# alimentadorV5.net
KiCad netlist of a schematic drawn in EAGLE
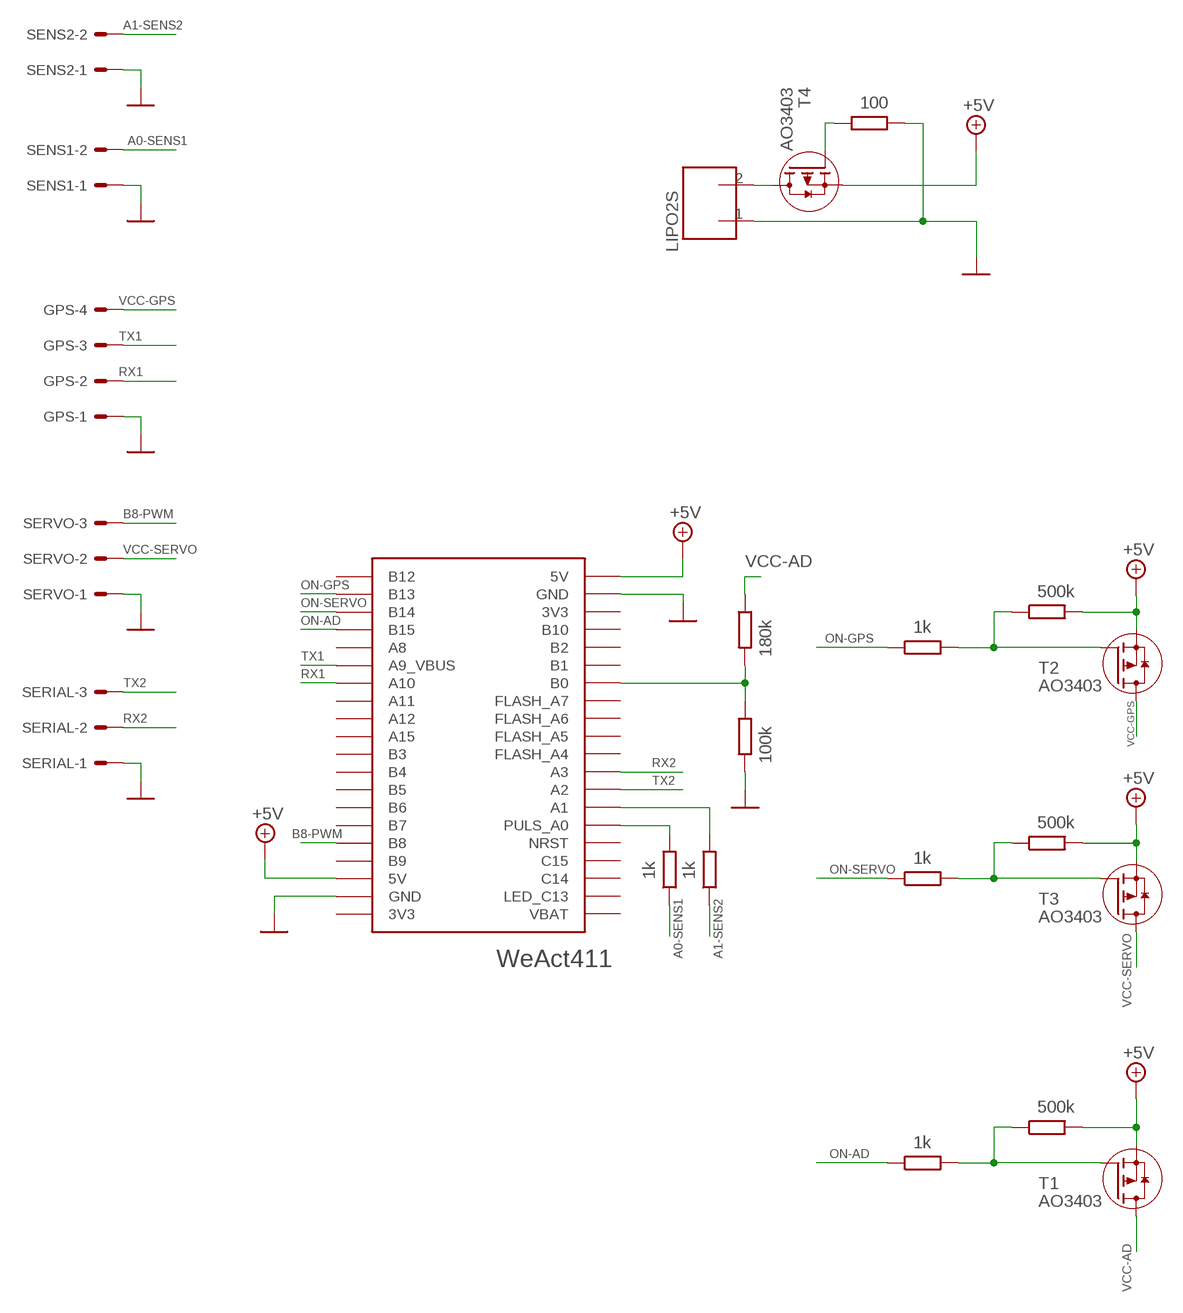
[diagram p0: schematic, sheet 1]

(export (version "E")
  (design (tool "Eeschema 10.0.6"))
  (components
    (comp (ref "GPS")
      (value "22-27-2041-04")
      (footprint "eagle-import:6410-04")
      (libsource (lib "eagle-import") (part "22-?-0427-2041"))
    )
    (comp (ref "LIPO2S")
      (value "CONECTOR_2P-3.81")
      (footprint "eagle-import:CON2P-3.81")
      (libsource (lib "eagle-import") (part "CONECTOR_2P-3.81"))
    )
    (comp (ref "R1")
      (value "500k")
      (footprint "eagle-import:R1206")
      (libsource (lib "eagle-import") (part "R-EU_R1206"))
    )
    (comp (ref "R2")
      (value "100k")
      (footprint "eagle-import:R1206")
      (libsource (lib "eagle-import") (part "R-EU_R1206"))
    )
    (comp (ref "R3")
      (value "180k")
      (footprint "eagle-import:R1206")
      (libsource (lib "eagle-import") (part "R-EU_R1206"))
    )
    (comp (ref "R4")
      (value "1k")
      (footprint "eagle-import:R1206")
      (libsource (lib "eagle-import") (part "R-EU_R1206"))
    )
    (comp (ref "R5")
      (value "500k")
      (footprint "eagle-import:R1206")
      (libsource (lib "eagle-import") (part "R-EU_R1206"))
    )
    (comp (ref "R6")
      (value "1k")
      (footprint "eagle-import:R1206")
      (libsource (lib "eagle-import") (part "R-EU_R1206"))
    )
    (comp (ref "R7")
      (value "100")
      (footprint "eagle-import:R1206")
      (libsource (lib "eagle-import") (part "R-EU_R1206"))
    )
    (comp (ref "R11")
      (value "500k")
      (footprint "eagle-import:R1206")
      (libsource (lib "eagle-import") (part "R-EU_R1206"))
    )
    (comp (ref "R12")
      (value "1k")
      (footprint "eagle-import:R1206")
      (libsource (lib "eagle-import") (part "R-EU_R1206"))
    )
    (comp (ref "R13")
      (value "1k")
      (footprint "eagle-import:R1206")
      (libsource (lib "eagle-import") (part "R-EU_R1206"))
    )
    (comp (ref "R14")
      (value "1k")
      (footprint "eagle-import:R1206")
      (libsource (lib "eagle-import") (part "R-EU_R1206"))
    )
    (comp (ref "SENS1")
      (value "22-27-2021-02")
      (footprint "eagle-import:6410-02")
      (libsource (lib "eagle-import") (part "22-?-0227-2021"))
    )
    (comp (ref "SENS2")
      (value "22-27-2021-02")
      (footprint "eagle-import:6410-02")
      (libsource (lib "eagle-import") (part "22-?-0227-2021"))
    )
    (comp (ref "SERIAL")
      (value "22-27-2031-03")
      (footprint "eagle-import:6410-03")
      (libsource (lib "eagle-import") (part "22-?-0327-2031"))
    )
    (comp (ref "SERVO")
      (value "22-27-2031-03")
      (footprint "eagle-import:6410-03")
      (libsource (lib "eagle-import") (part "22-?-0327-2031"))
    )
    (comp (ref "T1")
      (value "AO3403")
      (footprint "eagle-import:SOT23")
      (libsource (lib "eagle-import") (part "AO3403"))
    )
    (comp (ref "T2")
      (value "AO3403")
      (footprint "eagle-import:SOT23")
      (libsource (lib "eagle-import") (part "AO3403"))
    )
    (comp (ref "T3")
      (value "AO3403")
      (footprint "eagle-import:SOT23")
      (libsource (lib "eagle-import") (part "AO3403"))
    )
    (comp (ref "T4")
      (value "AO3403")
      (footprint "eagle-import:SOT23")
      (libsource (lib "eagle-import") (part "AO3403"))
    )
    (comp (ref "U$2")
      (value "WEACT411")
      (footprint "eagle-import:WEACT411")
      (libsource (lib "eagle-import") (part "WEACT411"))
    )
  )
  (nets
    (net (code "1") (name "+5V") (class "Default")
      (node (ref "R1") (pin "2") (pinfunction "2_2") (pintype "passive"))
      (node (ref "R11") (pin "2") (pinfunction "2_2") (pintype "passive"))
      (node (ref "R5") (pin "2") (pinfunction "2_2") (pintype "passive"))
      (node (ref "T1") (pin "2") (pinfunction "S_2") (pintype "passive"))
      (node (ref "T2") (pin "2") (pinfunction "S_2") (pintype "passive"))
      (node (ref "T3") (pin "2") (pinfunction "S_2") (pintype "passive"))
      (node (ref "T4") (pin "2") (pinfunction "S_2") (pintype "passive"))
      (node (ref "U$2") (pin "5V@1") (pinfunction "5V_5V@1") (pintype "power_in"))
      (node (ref "U$2") (pin "5V@2") (pinfunction "5V_5V@2") (pintype "power_in"))
    )
    (net (code "2") (name "/A0-SENS1") (class "Default")
      (node (ref "R13") (pin "1") (pinfunction "1_1") (pintype "passive"))
      (node (ref "SENS1") (pin "2") (pinfunction "S_2") (pintype "passive"))
    )
    (net (code "3") (name "/A1-SENS2") (class "Default")
      (node (ref "R14") (pin "1") (pinfunction "1_1") (pintype "passive"))
      (node (ref "SENS2") (pin "2") (pinfunction "S_2") (pintype "passive"))
    )
    (net (code "4") (name "/B8-PWM") (class "Default")
      (node (ref "SERVO") (pin "3") (pinfunction "S_3") (pintype "passive"))
      (node (ref "U$2") (pin "B8") (pinfunction "B8_B8") (pintype "bidirectional"))
    )
    (net (code "5") (name "/ON-AD") (class "Default")
      (node (ref "R12") (pin "1") (pinfunction "1_1") (pintype "passive"))
      (node (ref "U$2") (pin "B15") (pinfunction "B15_B15") (pintype "bidirectional"))
    )
    (net (code "6") (name "/ON-GPS") (class "Default")
      (node (ref "R4") (pin "1") (pinfunction "1_1") (pintype "passive"))
      (node (ref "U$2") (pin "B13") (pinfunction "B13_B13") (pintype "bidirectional"))
    )
    (net (code "7") (name "/ON-SERVO") (class "Default")
      (node (ref "R6") (pin "1") (pinfunction "1_1") (pintype "passive"))
      (node (ref "U$2") (pin "B14") (pinfunction "B14_B14") (pintype "bidirectional"))
    )
    (net (code "8") (name "/RX1") (class "Default")
      (node (ref "GPS") (pin "2") (pinfunction "S_2") (pintype "passive"))
      (node (ref "U$2") (pin "A10") (pinfunction "A10_A10") (pintype "bidirectional"))
    )
    (net (code "9") (name "/RX2") (class "Default")
      (node (ref "SERIAL") (pin "2") (pinfunction "S_2") (pintype "passive"))
      (node (ref "U$2") (pin "A3") (pinfunction "A3_A3") (pintype "bidirectional"))
    )
    (net (code "10") (name "/TX1") (class "Default")
      (node (ref "GPS") (pin "3") (pinfunction "S_3") (pintype "passive"))
      (node (ref "U$2") (pin "A9") (pinfunction "A9_VBUS_A9") (pintype "bidirectional"))
    )
    (net (code "11") (name "/TX2") (class "Default")
      (node (ref "SERIAL") (pin "3") (pinfunction "S_3") (pintype "passive"))
      (node (ref "U$2") (pin "A2") (pinfunction "A2_A2") (pintype "bidirectional"))
    )
    (net (code "12") (name "/VBAT") (class "Default")
      (node (ref "U$2") (pin "VBAT") (pinfunction "VBAT_VBAT") (pintype "power_in"))
    )
    (net (code "13") (name "/VCC-AD") (class "Default")
      (node (ref "R3") (pin "1") (pinfunction "1_1") (pintype "passive"))
      (node (ref "T1") (pin "3") (pinfunction "D_3") (pintype "passive"))
    )
    (net (code "14") (name "/VCC-GPS") (class "Default")
      (node (ref "GPS") (pin "4") (pinfunction "S_4") (pintype "passive"))
      (node (ref "T2") (pin "3") (pinfunction "D_3") (pintype "passive"))
    )
    (net (code "15") (name "/VCC-SERVO") (class "Default")
      (node (ref "SERVO") (pin "2") (pinfunction "S_2") (pintype "passive"))
      (node (ref "T3") (pin "3") (pinfunction "D_3") (pintype "passive"))
    )
    (net (code "16") (name "GND") (class "Default")
      (node (ref "GPS") (pin "1") (pinfunction "S_1") (pintype "passive"))
      (node (ref "LIPO2S") (pin "1") (pinfunction "1_1") (pintype "bidirectional"))
      (node (ref "R2") (pin "2") (pinfunction "2_2") (pintype "passive"))
      (node (ref "R7") (pin "2") (pinfunction "2_2") (pintype "passive"))
      (node (ref "SENS1") (pin "1") (pinfunction "S_1") (pintype "passive"))
      (node (ref "SENS2") (pin "1") (pinfunction "S_1") (pintype "passive"))
      (node (ref "SERIAL") (pin "1") (pinfunction "S_1") (pintype "passive"))
      (node (ref "SERVO") (pin "1") (pinfunction "S_1") (pintype "passive"))
      (node (ref "U$2") (pin "GND@1") (pinfunction "GND_GND@1") (pintype "power_in"))
      (node (ref "U$2") (pin "GND@2") (pinfunction "GND_GND@2") (pintype "power_in"))
    )
    (net (code "17") (name "Net-(R2-Pad1)") (class "Default")
      (node (ref "R2") (pin "1") (pinfunction "1_1") (pintype "passive"))
      (node (ref "R3") (pin "2") (pinfunction "2_2") (pintype "passive"))
      (node (ref "U$2") (pin "B0") (pinfunction "B0_B0") (pintype "bidirectional"))
    )
    (net (code "18") (name "Net-(R14-Pad2)") (class "Default")
      (node (ref "R14") (pin "2") (pinfunction "2_2") (pintype "passive"))
      (node (ref "U$2") (pin "A1") (pinfunction "A1_A1") (pintype "bidirectional"))
    )
    (net (code "19") (name "Net-(T1-G)") (class "Default")
      (node (ref "R11") (pin "1") (pinfunction "1_1") (pintype "passive"))
      (node (ref "R12") (pin "2") (pinfunction "2_2") (pintype "passive"))
      (node (ref "T1") (pin "1") (pinfunction "G_1") (pintype "passive"))
    )
    (net (code "20") (name "Net-(T2-G)") (class "Default")
      (node (ref "R1") (pin "1") (pinfunction "1_1") (pintype "passive"))
      (node (ref "R4") (pin "2") (pinfunction "2_2") (pintype "passive"))
      (node (ref "T2") (pin "1") (pinfunction "G_1") (pintype "passive"))
    )
    (net (code "21") (name "Net-(T3-G)") (class "Default")
      (node (ref "R5") (pin "1") (pinfunction "1_1") (pintype "passive"))
      (node (ref "R6") (pin "2") (pinfunction "2_2") (pintype "passive"))
      (node (ref "T3") (pin "1") (pinfunction "G_1") (pintype "passive"))
    )
    (net (code "22") (name "Net-(T4-D)") (class "Default")
      (node (ref "LIPO2S") (pin "2") (pinfunction "2_2") (pintype "bidirectional"))
      (node (ref "T4") (pin "3") (pinfunction "D_3") (pintype "passive"))
    )
    (net (code "23") (name "Net-(T4-G)") (class "Default")
      (node (ref "R7") (pin "1") (pinfunction "1_1") (pintype "passive"))
      (node (ref "T4") (pin "1") (pinfunction "G_1") (pintype "passive"))
    )
    (net (code "24") (name "Net-(U$2-PULS_A0)") (class "Default")
      (node (ref "R13") (pin "2") (pinfunction "2_2") (pintype "passive"))
      (node (ref "U$2") (pin "A0") (pinfunction "PULS_A0_A0") (pintype "bidirectional"))
    )
    (net (code "25") (name "unconnected-(U$2-3V3-Pad3V3@1)") (class "Default")
      (node (ref "U$2") (pin "3V3@1") (pinfunction "3V3_3V3@1") (pintype "bidirectional"))
    )
    (net (code "26") (name "unconnected-(U$2-3V3-Pad3V3@2)") (class "Default")
      (node (ref "U$2") (pin "3V3@2") (pinfunction "3V3_3V3@2") (pintype "bidirectional"))
    )
    (net (code "27") (name "unconnected-(U$2-FLASH_A4-PadA4)") (class "Default")
      (node (ref "U$2") (pin "A4") (pinfunction "FLASH_A4_A4") (pintype "bidirectional"))
    )
    (net (code "28") (name "unconnected-(U$2-FLASH_A5-PadA5)") (class "Default")
      (node (ref "U$2") (pin "A5") (pinfunction "FLASH_A5_A5") (pintype "bidirectional"))
    )
    (net (code "29") (name "unconnected-(U$2-FLASH_A6-PadA6)") (class "Default")
      (node (ref "U$2") (pin "A6") (pinfunction "FLASH_A6_A6") (pintype "bidirectional"))
    )
    (net (code "30") (name "unconnected-(U$2-FLASH_A7-PadA7)") (class "Default")
      (node (ref "U$2") (pin "A7") (pinfunction "FLASH_A7_A7") (pintype "bidirectional"))
    )
    (net (code "31") (name "unconnected-(U$2-LED_C13-PadC13)") (class "Default")
      (node (ref "U$2") (pin "C13") (pinfunction "LED_C13_C13") (pintype "bidirectional"))
    )
    (net (code "32") (name "unconnected-(U$2-PadA8)") (class "Default")
      (node (ref "U$2") (pin "A8") (pinfunction "A8_A8") (pintype "bidirectional"))
    )
    (net (code "33") (name "unconnected-(U$2-PadA11)") (class "Default")
      (node (ref "U$2") (pin "A11") (pinfunction "A11_A11") (pintype "bidirectional"))
    )
    (net (code "34") (name "unconnected-(U$2-PadA12)") (class "Default")
      (node (ref "U$2") (pin "A12") (pinfunction "A12_A12") (pintype "bidirectional"))
    )
    (net (code "35") (name "unconnected-(U$2-PadA15)") (class "Default")
      (node (ref "U$2") (pin "A15") (pinfunction "A15_A15") (pintype "bidirectional"))
    )
    (net (code "36") (name "unconnected-(U$2-PadB1)") (class "Default")
      (node (ref "U$2") (pin "B1") (pinfunction "B1_B1") (pintype "bidirectional"))
    )
    (net (code "37") (name "unconnected-(U$2-PadB2)") (class "Default")
      (node (ref "U$2") (pin "B2") (pinfunction "B2_B2") (pintype "bidirectional"))
    )
    (net (code "38") (name "unconnected-(U$2-PadB3)") (class "Default")
      (node (ref "U$2") (pin "B3") (pinfunction "B3_B3") (pintype "bidirectional"))
    )
    (net (code "39") (name "unconnected-(U$2-PadB4)") (class "Default")
      (node (ref "U$2") (pin "B4") (pinfunction "B4_B4") (pintype "bidirectional"))
    )
    (net (code "40") (name "unconnected-(U$2-PadB5)") (class "Default")
      (node (ref "U$2") (pin "B5") (pinfunction "B5_B5") (pintype "bidirectional"))
    )
    (net (code "41") (name "unconnected-(U$2-PadB6)") (class "Default")
      (node (ref "U$2") (pin "B6") (pinfunction "B6_B6") (pintype "bidirectional"))
    )
    (net (code "42") (name "unconnected-(U$2-PadB7)") (class "Default")
      (node (ref "U$2") (pin "B7") (pinfunction "B7_B7") (pintype "bidirectional"))
    )
    (net (code "43") (name "unconnected-(U$2-PadB9)") (class "Default")
      (node (ref "U$2") (pin "B9") (pinfunction "B9_B9") (pintype "bidirectional"))
    )
    (net (code "44") (name "unconnected-(U$2-PadB10)") (class "Default")
      (node (ref "U$2") (pin "B10") (pinfunction "B10_B10") (pintype "bidirectional"))
    )
    (net (code "45") (name "unconnected-(U$2-PadB12)") (class "Default")
      (node (ref "U$2") (pin "B12") (pinfunction "B12_B12") (pintype "bidirectional"))
    )
    (net (code "46") (name "unconnected-(U$2-PadC14)") (class "Default")
      (node (ref "U$2") (pin "C14") (pinfunction "C14_C14") (pintype "bidirectional"))
    )
    (net (code "47") (name "unconnected-(U$2-PadC15)") (class "Default")
      (node (ref "U$2") (pin "C15") (pinfunction "C15_C15") (pintype "bidirectional"))
    )
    (net (code "48") (name "unconnected-(U$2-PadNRST)") (class "Default")
      (node (ref "U$2") (pin "NRST") (pinfunction "NRST_NRST") (pintype "bidirectional"))
    )
  )
)
